# USB_to_UART_Adapter.net
KiCad netlist of a schematic drawn in EAGLE
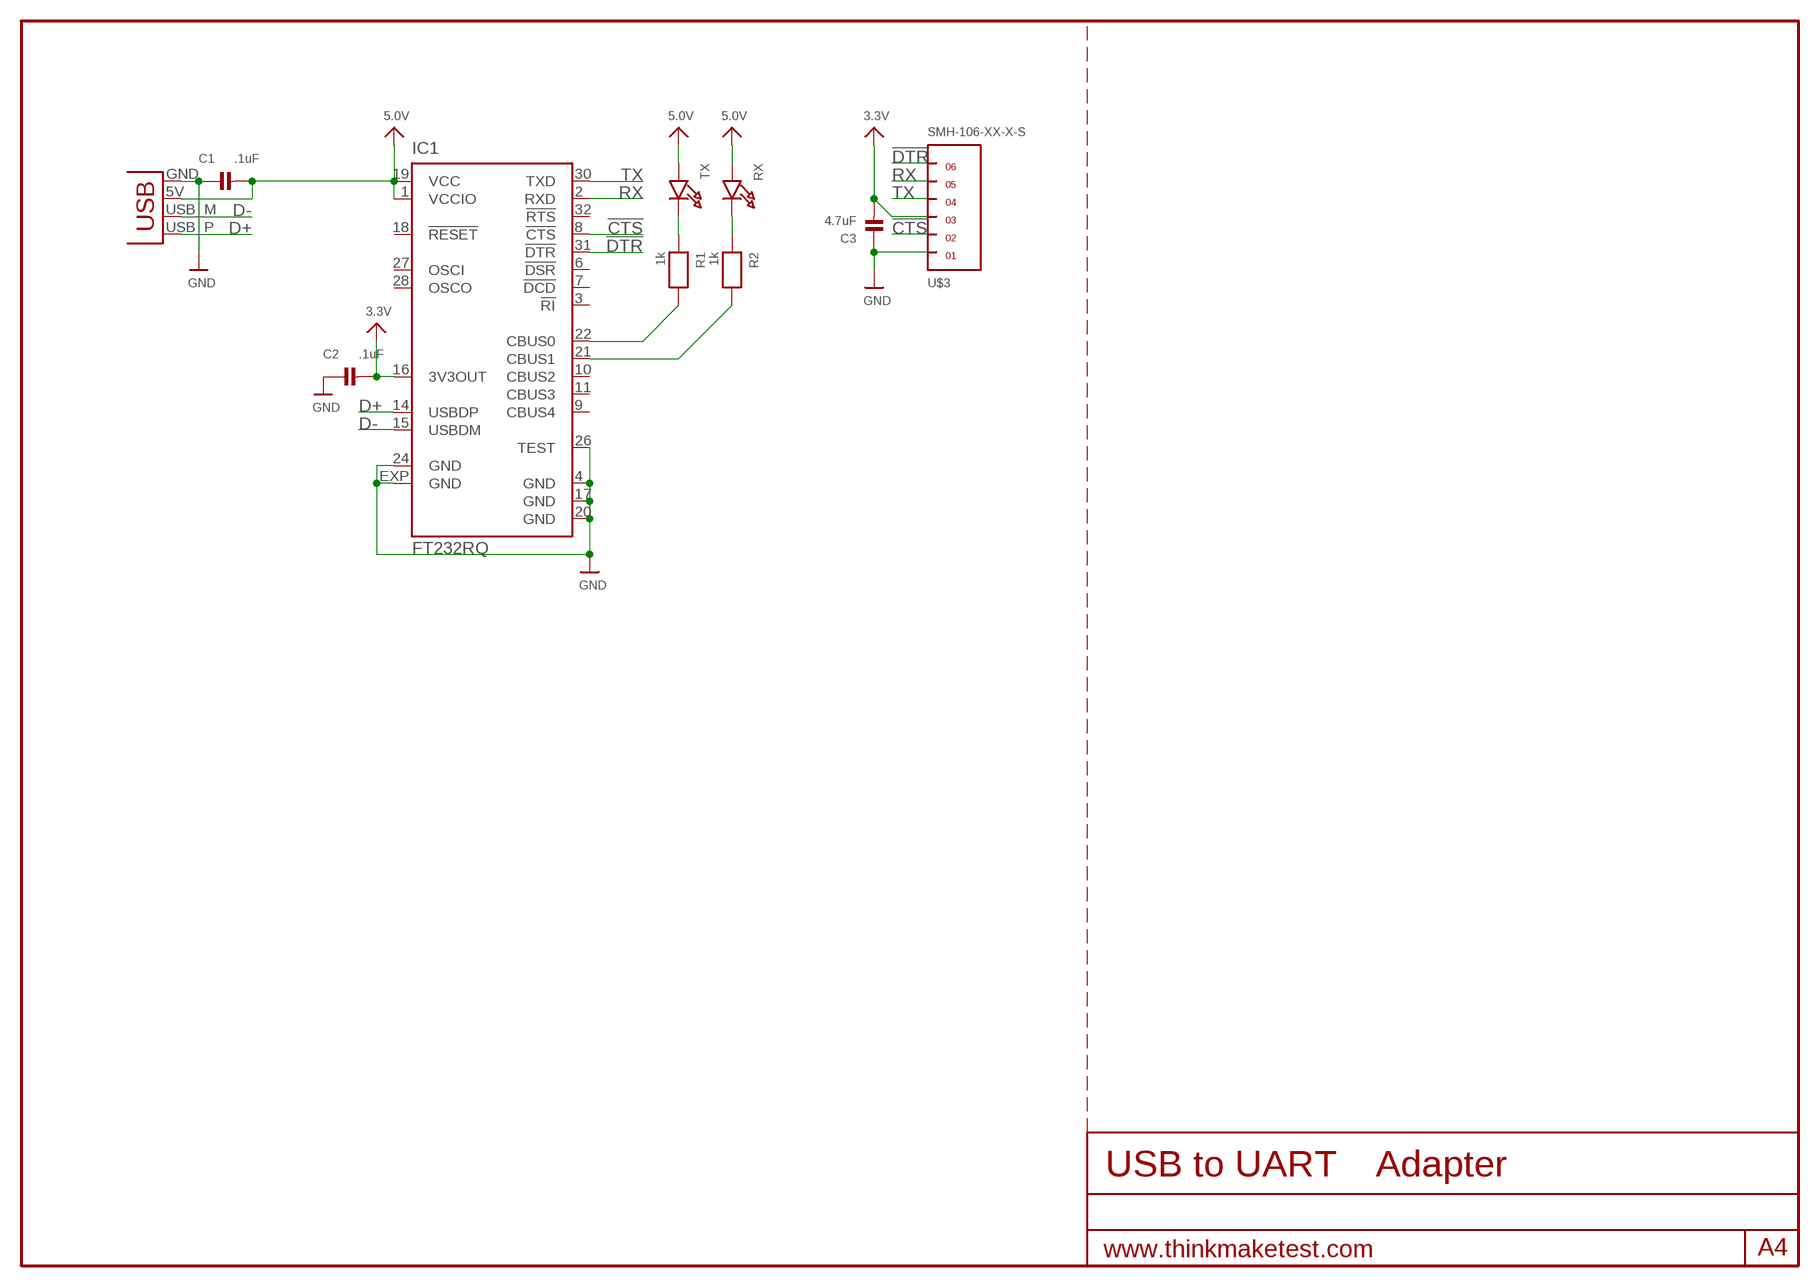
[diagram p0: schematic, sheet 1]

(export (version "E")
  (design (tool "Eeschema 10.0.6"))
  (components
    (comp (ref "C1")
      (value ".1uF")
      (footprint "eagle-import:0402")
      (libsource (lib "eagle-import") (part "CAP_CERAMIC0402"))
    )
    (comp (ref "C2")
      (value ".1uF")
      (footprint "eagle-import:0402")
      (libsource (lib "eagle-import") (part "CAP_CERAMIC0402"))
    )
    (comp (ref "C3")
      (value "4.7uF")
      (footprint "eagle-import:0603")
      (libsource (lib "eagle-import") (part "CAP_CERAMIC0603"))
    )
    (comp (ref "IC1")
      (value "FT232RQ")
      (footprint "eagle-import:QFN32")
      (libsource (lib "eagle-import") (part "FT232RQ"))
    )
    (comp (ref "R1")
      (value "1k")
      (footprint "eagle-import:0402")
      (libsource (lib "eagle-import") (part "RESISTOR0402"))
    )
    (comp (ref "R2")
      (value "1k")
      (footprint "eagle-import:0402")
      (libsource (lib "eagle-import") (part "RESISTOR0402"))
    )
    (comp (ref "RX")
      (value "LED0603")
      (footprint "eagle-import:CHIPLED_0603")
      (libsource (lib "eagle-import") (part "LED0603"))
    )
    (comp (ref "TX")
      (value "LED0603")
      (footprint "eagle-import:CHIPLED_0603")
      (libsource (lib "eagle-import") (part "LED0603"))
    )
    (comp (ref "U$3")
      (value "SMH-106-XX-X-S")
      (footprint "eagle-import:SMH-106-XX-X-S")
      (libsource (lib "eagle-import") (part "SMH-106-XX-X-S"))
    )
    (comp (ref "X1")
      (value "USBPCB")
      (footprint "eagle-import:USB-A-PCB")
      (libsource (lib "eagle-import") (part "USBPCB"))
    )
  )
  (nets
    (net (code "1") (name "/D+") (class "Default")
      (node (ref "IC1") (pin "14") (pinfunction "USBDP_14") (pintype "bidirectional"))
      (node (ref "X1") (pin "USB_P") (pinfunction "D+_USB_P") (pintype "bidirectional"))
    )
    (net (code "2") (name "/D-") (class "Default")
      (node (ref "IC1") (pin "15") (pinfunction "USBDM_15") (pintype "bidirectional"))
      (node (ref "X1") (pin "USB_M") (pinfunction "D-_USB_M") (pintype "bidirectional"))
    )
    (net (code "3") (name "/RX") (class "Default")
      (node (ref "IC1") (pin "2") (pinfunction "RXD_2") (pintype "input"))
      (node (ref "U$3") (pin "5") (pinfunction "P$5_5") (pintype "bidirectional"))
    )
    (net (code "4") (name "/TX") (class "Default")
      (node (ref "IC1") (pin "30") (pinfunction "TXD_30") (pintype "output"))
      (node (ref "U$3") (pin "4") (pinfunction "P$4_4") (pintype "bidirectional"))
    )
    (net (code "5") (name "/~{CTS}") (class "Default")
      (node (ref "IC1") (pin "8") (pinfunction "~{CTS}_8") (pintype "input"))
      (node (ref "U$3") (pin "2") (pinfunction "P$2_2") (pintype "bidirectional"))
    )
    (net (code "6") (name "/~{DTR}") (class "Default")
      (node (ref "IC1") (pin "31") (pinfunction "~{DTR}_31") (pintype "output"))
      (node (ref "U$3") (pin "6") (pinfunction "P$6_6") (pintype "bidirectional"))
    )
    (net (code "7") (name "3.3V") (class "Default")
      (node (ref "C2") (pin "2") (pinfunction "P$2_2") (pintype "passive"))
      (node (ref "C3") (pin "2") (pinfunction "P$2_2") (pintype "passive"))
      (node (ref "IC1") (pin "16") (pinfunction "3V3OUT_16") (pintype "output"))
      (node (ref "U$3") (pin "3") (pinfunction "P$3_3") (pintype "bidirectional"))
    )
    (net (code "8") (name "5.0V") (class "Default")
      (node (ref "C1") (pin "2") (pinfunction "P$2_2") (pintype "passive"))
      (node (ref "IC1") (pin "1") (pinfunction "VCCIO_1") (pintype "power_in"))
      (node (ref "IC1") (pin "19") (pinfunction "VCC_19") (pintype "power_in"))
      (node (ref "RX") (pin "A") (pinfunction "A_A") (pintype "passive"))
      (node (ref "TX") (pin "A") (pinfunction "A_A") (pintype "passive"))
      (node (ref "X1") (pin "5V") (pinfunction "VBUS_5V") (pintype "bidirectional"))
    )
    (net (code "9") (name "GND") (class "Default")
      (node (ref "C1") (pin "1") (pinfunction "P$1_1") (pintype "passive"))
      (node (ref "C2") (pin "1") (pinfunction "P$1_1") (pintype "passive"))
      (node (ref "C3") (pin "1") (pinfunction "P$1_1") (pintype "passive"))
      (node (ref "IC1") (pin "17") (pinfunction "GND_17") (pintype "power_in"))
      (node (ref "IC1") (pin "20") (pinfunction "GND_20") (pintype "power_in"))
      (node (ref "IC1") (pin "24") (pinfunction "GND_24") (pintype "power_in"))
      (node (ref "IC1") (pin "26") (pinfunction "TEST_26") (pintype "input"))
      (node (ref "IC1") (pin "4") (pinfunction "GND_4") (pintype "power_in"))
      (node (ref "IC1") (pin "EXP") (pinfunction "GND_EXP") (pintype "power_in"))
      (node (ref "U$3") (pin "1") (pinfunction "P$1_1") (pintype "bidirectional"))
      (node (ref "X1") (pin "GND") (pinfunction "GND_GND") (pintype "bidirectional"))
    )
    (net (code "10") (name "Net-(IC1-CBUS0)") (class "Default")
      (node (ref "IC1") (pin "22") (pinfunction "CBUS0_22") (pintype "bidirectional"))
      (node (ref "R1") (pin "2") (pinfunction "2_2") (pintype "passive"))
    )
    (net (code "11") (name "Net-(IC1-CBUS1)") (class "Default")
      (node (ref "IC1") (pin "21") (pinfunction "CBUS1_21") (pintype "bidirectional"))
      (node (ref "R2") (pin "2") (pinfunction "2_2") (pintype "passive"))
    )
    (net (code "12") (name "Net-(R1-Pad1)") (class "Default")
      (node (ref "R1") (pin "1") (pinfunction "1_1") (pintype "passive"))
      (node (ref "TX") (pin "C") (pinfunction "C_C") (pintype "passive"))
    )
    (net (code "13") (name "Net-(R2-Pad1)") (class "Default")
      (node (ref "R2") (pin "1") (pinfunction "1_1") (pintype "passive"))
      (node (ref "RX") (pin "C") (pinfunction "C_C") (pintype "passive"))
    )
    (net (code "14") (name "unconnected-(IC1-CBUS2-Pad10)") (class "Default")
      (node (ref "IC1") (pin "10") (pinfunction "CBUS2_10") (pintype "bidirectional"))
    )
    (net (code "15") (name "unconnected-(IC1-CBUS3-Pad11)") (class "Default")
      (node (ref "IC1") (pin "11") (pinfunction "CBUS3_11") (pintype "bidirectional"))
    )
    (net (code "16") (name "unconnected-(IC1-CBUS4-Pad9)") (class "Default")
      (node (ref "IC1") (pin "9") (pinfunction "CBUS4_9") (pintype "bidirectional"))
    )
    (net (code "17") (name "unconnected-(IC1-OSCI-Pad27)") (class "Default")
      (node (ref "IC1") (pin "27") (pinfunction "OSCI_27") (pintype "input"))
    )
    (net (code "18") (name "unconnected-(IC1-OSCO-Pad28)") (class "Default")
      (node (ref "IC1") (pin "28") (pinfunction "OSCO_28") (pintype "output"))
    )
    (net (code "19") (name "unconnected-(IC1-~{DCD}-Pad7)") (class "Default")
      (node (ref "IC1") (pin "7") (pinfunction "~{DCD}_7") (pintype "input"))
    )
    (net (code "20") (name "unconnected-(IC1-~{DSR}-Pad6)") (class "Default")
      (node (ref "IC1") (pin "6") (pinfunction "~{DSR}_6") (pintype "input"))
    )
    (net (code "21") (name "unconnected-(IC1-~{RESET}-Pad18)") (class "Default")
      (node (ref "IC1") (pin "18") (pinfunction "~{RESET}_18") (pintype "input"))
    )
    (net (code "22") (name "unconnected-(IC1-~{RI}-Pad3)") (class "Default")
      (node (ref "IC1") (pin "3") (pinfunction "~{RI}_3") (pintype "input"))
    )
    (net (code "23") (name "unconnected-(IC1-~{RTS}-Pad32)") (class "Default")
      (node (ref "IC1") (pin "32") (pinfunction "~{RTS}_32") (pintype "output"))
    )
  )
)
